# Sheet1.net
KiCad netlist of a schematic drawn in Altium Designer
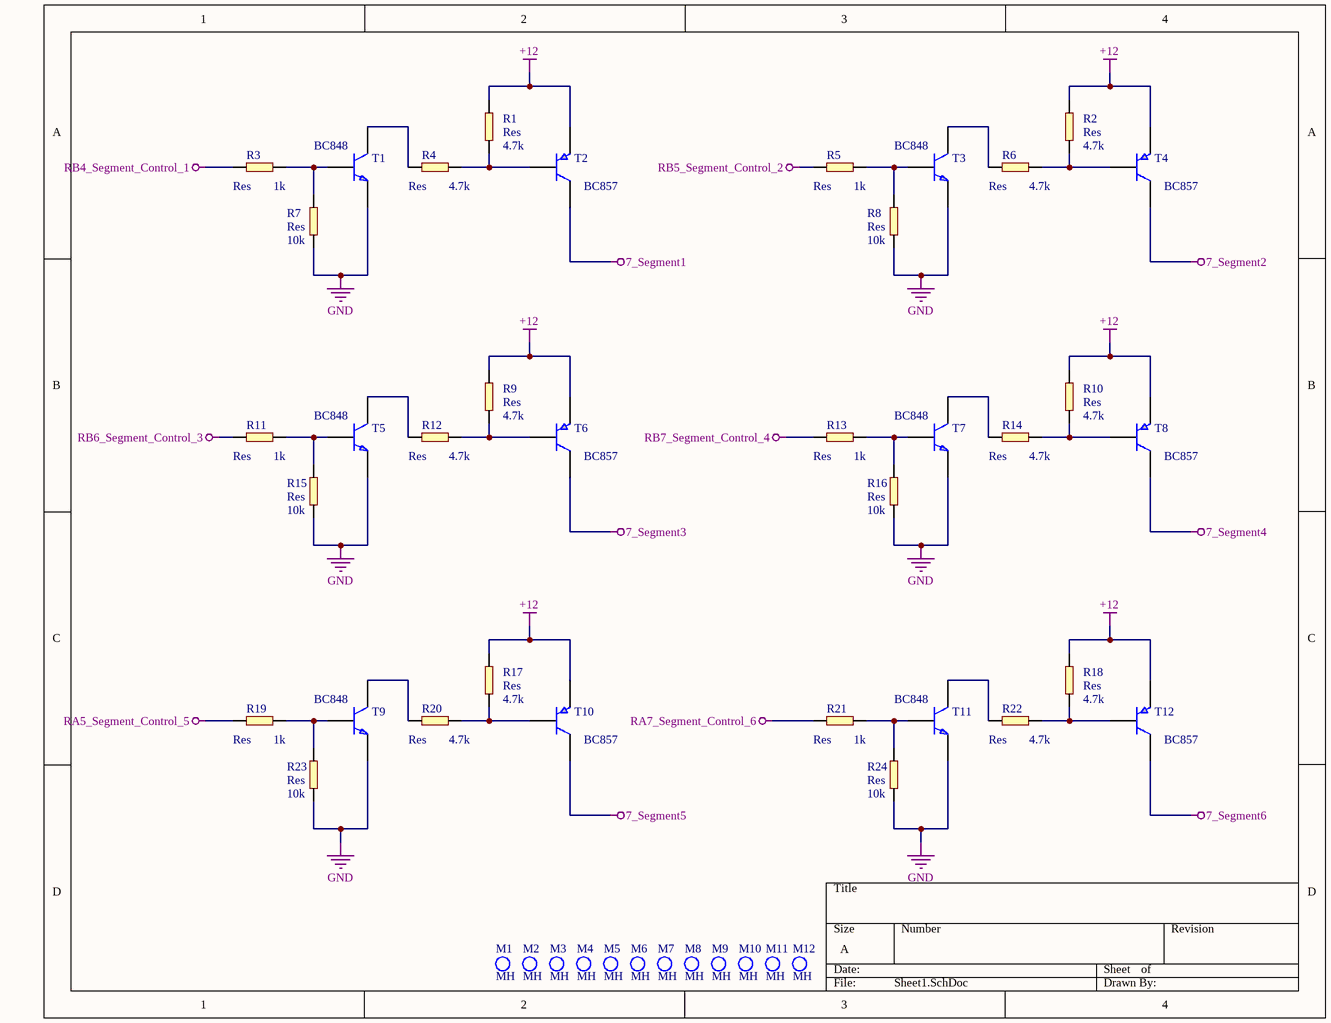
[diagram p0: Sheet1.SchDoc]

(export (version "E")
  (design (tool "Eeschema 10.0.6"))
  (components
    (comp (ref "M1")
      (value "MH")
      (footprint "Mounting hole")
      (libsource (lib "Dinesh_New_Integrated_Library") (part "MH"))
    )
    (comp (ref "M2")
      (value "MH")
      (footprint "Mounting hole")
      (libsource (lib "Dinesh_New_Integrated_Library") (part "MH"))
    )
    (comp (ref "M3")
      (value "MH")
      (footprint "Mounting hole")
      (libsource (lib "Dinesh_New_Integrated_Library") (part "MH"))
    )
    (comp (ref "M4")
      (value "MH")
      (footprint "Mounting hole")
      (libsource (lib "Dinesh_New_Integrated_Library") (part "MH"))
    )
    (comp (ref "M5")
      (value "MH")
      (footprint "Mounting hole")
      (libsource (lib "Dinesh_New_Integrated_Library") (part "MH"))
    )
    (comp (ref "M6")
      (value "MH")
      (footprint "Mounting hole")
      (libsource (lib "Dinesh_New_Integrated_Library") (part "MH"))
    )
    (comp (ref "M7")
      (value "MH")
      (footprint "Mounting hole")
      (libsource (lib "Dinesh_New_Integrated_Library") (part "MH"))
    )
    (comp (ref "M8")
      (value "MH")
      (footprint "Mounting hole")
      (libsource (lib "Dinesh_New_Integrated_Library") (part "MH"))
    )
    (comp (ref "M9")
      (value "MH")
      (footprint "Mounting hole")
      (libsource (lib "Dinesh_New_Integrated_Library") (part "MH"))
    )
    (comp (ref "M10")
      (value "MH")
      (footprint "Mounting hole")
      (libsource (lib "Dinesh_New_Integrated_Library") (part "MH"))
    )
    (comp (ref "M11")
      (value "MH")
      (footprint "Mounting hole")
      (libsource (lib "Dinesh_New_Integrated_Library") (part "MH"))
    )
    (comp (ref "M12")
      (value "MH")
      (footprint "Mounting hole")
      (libsource (lib "Dinesh_New_Integrated_Library") (part "MH"))
    )
    (comp (ref "R1")
      (value "Res")
      (footprint "RES0805")
      (description "Res0805")
      (fields (field (name "ALTIUM_VALUE") "4.7k"))
      (libsource (lib "") (part "Resistor_2"))
    )
    (comp (ref "R2")
      (value "Res")
      (footprint "RES0805")
      (description "Res0805")
      (fields (field (name "ALTIUM_VALUE") "4.7k"))
      (libsource (lib "") (part "Resistor_2"))
    )
    (comp (ref "R3")
      (value "Res")
      (footprint "RES0805")
      (description "Res0805")
      (fields (field (name "ALTIUM_VALUE") "1k"))
      (libsource (lib "") (part "Resistor_1"))
    )
    (comp (ref "R4")
      (value "Res")
      (footprint "RES0805")
      (description "Res0805")
      (fields (field (name "ALTIUM_VALUE") "4.7k"))
      (libsource (lib "") (part "Resistor_1"))
    )
    (comp (ref "R5")
      (value "Res")
      (footprint "RES0805")
      (description "Res0805")
      (fields (field (name "ALTIUM_VALUE") "1k"))
      (libsource (lib "") (part "Resistor_1"))
    )
    (comp (ref "R6")
      (value "Res")
      (footprint "RES0805")
      (description "Res0805")
      (fields (field (name "ALTIUM_VALUE") "4.7k"))
      (libsource (lib "") (part "Resistor_1"))
    )
    (comp (ref "R7")
      (value "Res")
      (footprint "RES0805")
      (description "Res0805")
      (fields (field (name "ALTIUM_VALUE") "10k"))
      (libsource (lib "Dinesh_New_Integrated_Library") (part "Resistor"))
    )
    (comp (ref "R8")
      (value "Res")
      (footprint "RES0805")
      (description "Res0805")
      (fields (field (name "ALTIUM_VALUE") "10k"))
      (libsource (lib "Dinesh_New_Integrated_Library") (part "Resistor"))
    )
    (comp (ref "R9")
      (value "Res")
      (footprint "RES0805")
      (description "Res0805")
      (fields (field (name "ALTIUM_VALUE") "4.7k"))
      (libsource (lib "") (part "Resistor_2"))
    )
    (comp (ref "R10")
      (value "Res")
      (footprint "RES0805")
      (description "Res0805")
      (fields (field (name "ALTIUM_VALUE") "4.7k"))
      (libsource (lib "") (part "Resistor_2"))
    )
    (comp (ref "R11")
      (value "Res")
      (footprint "RES0805")
      (description "Res0805")
      (fields (field (name "ALTIUM_VALUE") "1k"))
      (libsource (lib "") (part "Resistor_1"))
    )
    (comp (ref "R12")
      (value "Res")
      (footprint "RES0805")
      (description "Res0805")
      (fields (field (name "ALTIUM_VALUE") "4.7k"))
      (libsource (lib "") (part "Resistor_1"))
    )
    (comp (ref "R13")
      (value "Res")
      (footprint "RES0805")
      (description "Res0805")
      (fields (field (name "ALTIUM_VALUE") "1k"))
      (libsource (lib "") (part "Resistor_1"))
    )
    (comp (ref "R14")
      (value "Res")
      (footprint "RES0805")
      (description "Res0805")
      (fields (field (name "ALTIUM_VALUE") "4.7k"))
      (libsource (lib "") (part "Resistor_1"))
    )
    (comp (ref "R15")
      (value "Res")
      (footprint "RES0805")
      (description "Res0805")
      (fields (field (name "ALTIUM_VALUE") "10k"))
      (libsource (lib "Dinesh_New_Integrated_Library") (part "Resistor"))
    )
    (comp (ref "R16")
      (value "Res")
      (footprint "RES0805")
      (description "Res0805")
      (fields (field (name "ALTIUM_VALUE") "10k"))
      (libsource (lib "Dinesh_New_Integrated_Library") (part "Resistor"))
    )
    (comp (ref "R17")
      (value "Res")
      (footprint "RES0805")
      (description "Res0805")
      (fields (field (name "ALTIUM_VALUE") "4.7k"))
      (libsource (lib "") (part "Resistor_2"))
    )
    (comp (ref "R18")
      (value "Res")
      (footprint "RES0805")
      (description "Res0805")
      (fields (field (name "ALTIUM_VALUE") "4.7k"))
      (libsource (lib "") (part "Resistor_2"))
    )
    (comp (ref "R19")
      (value "Res")
      (footprint "RES0805")
      (description "Res0805")
      (fields (field (name "ALTIUM_VALUE") "1k"))
      (libsource (lib "") (part "Resistor_1"))
    )
    (comp (ref "R20")
      (value "Res")
      (footprint "RES0805")
      (description "Res0805")
      (fields (field (name "ALTIUM_VALUE") "4.7k"))
      (libsource (lib "") (part "Resistor_1"))
    )
    (comp (ref "R21")
      (value "Res")
      (footprint "RES0805")
      (description "Res0805")
      (fields (field (name "ALTIUM_VALUE") "1k"))
      (libsource (lib "") (part "Resistor_1"))
    )
    (comp (ref "R22")
      (value "Res")
      (footprint "RES0805")
      (description "Res0805")
      (fields (field (name "ALTIUM_VALUE") "4.7k"))
      (libsource (lib "") (part "Resistor_1"))
    )
    (comp (ref "R23")
      (value "Res")
      (footprint "RES0805")
      (description "Res0805")
      (fields (field (name "ALTIUM_VALUE") "10k"))
      (libsource (lib "Dinesh_New_Integrated_Library") (part "Resistor"))
    )
    (comp (ref "R24")
      (value "Res")
      (footprint "RES0805")
      (description "Res0805")
      (fields (field (name "ALTIUM_VALUE") "10k"))
      (libsource (lib "Dinesh_New_Integrated_Library") (part "Resistor"))
    )
    (comp (ref "T1")
      (value "BC848")
      (footprint "SOT23")
      (description "TRANSISTOR")
      (libsource (lib "Dinesh_New_Integrated_Library") (part "BC848"))
    )
    (comp (ref "T2")
      (value "BC857")
      (footprint "SOT23")
      (libsource (lib "Dinesh_New_Integrated_Library") (part "BC857"))
    )
    (comp (ref "T3")
      (value "BC848")
      (footprint "SOT23")
      (description "TRANSISTOR")
      (libsource (lib "Dinesh_New_Integrated_Library") (part "BC848"))
    )
    (comp (ref "T4")
      (value "BC857")
      (footprint "SOT23")
      (libsource (lib "Dinesh_New_Integrated_Library") (part "BC857"))
    )
    (comp (ref "T5")
      (value "BC848")
      (footprint "SOT23")
      (description "TRANSISTOR")
      (libsource (lib "Dinesh_New_Integrated_Library") (part "BC848"))
    )
    (comp (ref "T6")
      (value "BC857")
      (footprint "SOT23")
      (libsource (lib "Dinesh_New_Integrated_Library") (part "BC857"))
    )
    (comp (ref "T7")
      (value "BC848")
      (footprint "SOT23")
      (description "TRANSISTOR")
      (libsource (lib "Dinesh_New_Integrated_Library") (part "BC848"))
    )
    (comp (ref "T8")
      (value "BC857")
      (footprint "SOT23")
      (libsource (lib "Dinesh_New_Integrated_Library") (part "BC857"))
    )
    (comp (ref "T9")
      (value "BC848")
      (footprint "SOT23")
      (description "TRANSISTOR")
      (libsource (lib "Dinesh_New_Integrated_Library") (part "BC848"))
    )
    (comp (ref "T10")
      (value "BC857")
      (footprint "SOT23")
      (libsource (lib "Dinesh_New_Integrated_Library") (part "BC857"))
    )
    (comp (ref "T11")
      (value "BC848")
      (footprint "SOT23")
      (description "TRANSISTOR")
      (libsource (lib "Dinesh_New_Integrated_Library") (part "BC848"))
    )
    (comp (ref "T12")
      (value "BC857")
      (footprint "SOT23")
      (libsource (lib "Dinesh_New_Integrated_Library") (part "BC857"))
    )
  )
  (nets
    (net (code "1") (name "+12") (class "Default")
      (node (ref "R1") (pin "2") (pinfunction "b_2") (pintype "passive"))
      (node (ref "R10") (pin "2") (pinfunction "b_2") (pintype "passive"))
      (node (ref "R17") (pin "2") (pinfunction "b_2") (pintype "passive"))
      (node (ref "R18") (pin "2") (pinfunction "b_2") (pintype "passive"))
      (node (ref "R2") (pin "2") (pinfunction "b_2") (pintype "passive"))
      (node (ref "R9") (pin "2") (pinfunction "b_2") (pintype "passive"))
      (node (ref "T10") (pin "2") (pinfunction "E_2") (pintype "passive"))
      (node (ref "T12") (pin "2") (pinfunction "E_2") (pintype "passive"))
      (node (ref "T2") (pin "2") (pinfunction "E_2") (pintype "passive"))
      (node (ref "T4") (pin "2") (pinfunction "E_2") (pintype "passive"))
      (node (ref "T6") (pin "2") (pinfunction "E_2") (pintype "passive"))
      (node (ref "T8") (pin "2") (pinfunction "E_2") (pintype "passive"))
    )
    (net (code "2") (name "7_Segment1") (class "Default")
      (node (ref "T2") (pin "3") (pinfunction "C_3") (pintype "passive"))
    )
    (net (code "3") (name "7_Segment2") (class "Default")
      (node (ref "T4") (pin "3") (pinfunction "C_3") (pintype "passive"))
    )
    (net (code "4") (name "7_Segment3") (class "Default")
      (node (ref "T6") (pin "3") (pinfunction "C_3") (pintype "passive"))
    )
    (net (code "5") (name "7_Segment4") (class "Default")
      (node (ref "T8") (pin "3") (pinfunction "C_3") (pintype "passive"))
    )
    (net (code "6") (name "7_Segment5") (class "Default")
      (node (ref "T10") (pin "3") (pinfunction "C_3") (pintype "passive"))
    )
    (net (code "7") (name "7_Segment6") (class "Default")
      (node (ref "T12") (pin "3") (pinfunction "C_3") (pintype "passive"))
    )
    (net (code "8") (name "GND") (class "Default")
      (node (ref "R15") (pin "2") (pinfunction "b_2") (pintype "passive"))
      (node (ref "R16") (pin "2") (pinfunction "b_2") (pintype "passive"))
      (node (ref "R23") (pin "2") (pinfunction "b_2") (pintype "passive"))
      (node (ref "R24") (pin "2") (pinfunction "b_2") (pintype "passive"))
      (node (ref "R7") (pin "2") (pinfunction "b_2") (pintype "passive"))
      (node (ref "R8") (pin "2") (pinfunction "b_2") (pintype "passive"))
      (node (ref "T1") (pin "2") (pinfunction "E_2") (pintype "passive"))
      (node (ref "T11") (pin "2") (pinfunction "E_2") (pintype "passive"))
      (node (ref "T3") (pin "2") (pinfunction "E_2") (pintype "passive"))
      (node (ref "T5") (pin "2") (pinfunction "E_2") (pintype "passive"))
      (node (ref "T7") (pin "2") (pinfunction "E_2") (pintype "passive"))
      (node (ref "T9") (pin "2") (pinfunction "E_2") (pintype "passive"))
    )
    (net (code "9") (name "Net-(R1-a)") (class "Default")
      (node (ref "R1") (pin "1") (pinfunction "a_1") (pintype "passive"))
      (node (ref "R4") (pin "1") (pinfunction "a_1") (pintype "passive"))
      (node (ref "T2") (pin "1") (pinfunction "B_1") (pintype "passive"))
    )
    (net (code "10") (name "Net-(R2-a)") (class "Default")
      (node (ref "R2") (pin "1") (pinfunction "a_1") (pintype "passive"))
      (node (ref "R6") (pin "1") (pinfunction "a_1") (pintype "passive"))
      (node (ref "T4") (pin "1") (pinfunction "B_1") (pintype "passive"))
    )
    (net (code "11") (name "Net-(R3-a)") (class "Default")
      (node (ref "R3") (pin "1") (pinfunction "a_1") (pintype "passive"))
      (node (ref "R7") (pin "1") (pinfunction "a_1") (pintype "passive"))
      (node (ref "T1") (pin "1") (pinfunction "B_1") (pintype "passive"))
    )
    (net (code "12") (name "Net-(R4-b)") (class "Default")
      (node (ref "R4") (pin "2") (pinfunction "b_2") (pintype "passive"))
      (node (ref "T1") (pin "3") (pinfunction "C_3") (pintype "passive"))
    )
    (net (code "13") (name "Net-(R5-a)") (class "Default")
      (node (ref "R5") (pin "1") (pinfunction "a_1") (pintype "passive"))
      (node (ref "R8") (pin "1") (pinfunction "a_1") (pintype "passive"))
      (node (ref "T3") (pin "1") (pinfunction "B_1") (pintype "passive"))
    )
    (net (code "14") (name "Net-(R6-b)") (class "Default")
      (node (ref "R6") (pin "2") (pinfunction "b_2") (pintype "passive"))
      (node (ref "T3") (pin "3") (pinfunction "C_3") (pintype "passive"))
    )
    (net (code "15") (name "Net-(R10-a)") (class "Default")
      (node (ref "R10") (pin "1") (pinfunction "a_1") (pintype "passive"))
      (node (ref "R14") (pin "1") (pinfunction "a_1") (pintype "passive"))
      (node (ref "T8") (pin "1") (pinfunction "B_1") (pintype "passive"))
    )
    (net (code "16") (name "Net-(R11-a)") (class "Default")
      (node (ref "R11") (pin "1") (pinfunction "a_1") (pintype "passive"))
      (node (ref "R15") (pin "1") (pinfunction "a_1") (pintype "passive"))
      (node (ref "T5") (pin "1") (pinfunction "B_1") (pintype "passive"))
    )
    (net (code "17") (name "Net-(R12-a)") (class "Default")
      (node (ref "R12") (pin "1") (pinfunction "a_1") (pintype "passive"))
      (node (ref "R9") (pin "1") (pinfunction "a_1") (pintype "passive"))
      (node (ref "T6") (pin "1") (pinfunction "B_1") (pintype "passive"))
    )
    (net (code "18") (name "Net-(R12-b)") (class "Default")
      (node (ref "R12") (pin "2") (pinfunction "b_2") (pintype "passive"))
      (node (ref "T5") (pin "3") (pinfunction "C_3") (pintype "passive"))
    )
    (net (code "19") (name "Net-(R13-a)") (class "Default")
      (node (ref "R13") (pin "1") (pinfunction "a_1") (pintype "passive"))
      (node (ref "R16") (pin "1") (pinfunction "a_1") (pintype "passive"))
      (node (ref "T7") (pin "1") (pinfunction "B_1") (pintype "passive"))
    )
    (net (code "20") (name "Net-(R14-b)") (class "Default")
      (node (ref "R14") (pin "2") (pinfunction "b_2") (pintype "passive"))
      (node (ref "T7") (pin "3") (pinfunction "C_3") (pintype "passive"))
    )
    (net (code "21") (name "Net-(R17-a)") (class "Default")
      (node (ref "R17") (pin "1") (pinfunction "a_1") (pintype "passive"))
      (node (ref "R20") (pin "1") (pinfunction "a_1") (pintype "passive"))
      (node (ref "T10") (pin "1") (pinfunction "B_1") (pintype "passive"))
    )
    (net (code "22") (name "Net-(R18-a)") (class "Default")
      (node (ref "R18") (pin "1") (pinfunction "a_1") (pintype "passive"))
      (node (ref "R22") (pin "1") (pinfunction "a_1") (pintype "passive"))
      (node (ref "T12") (pin "1") (pinfunction "B_1") (pintype "passive"))
    )
    (net (code "23") (name "Net-(R19-a)") (class "Default")
      (node (ref "R19") (pin "1") (pinfunction "a_1") (pintype "passive"))
      (node (ref "R23") (pin "1") (pinfunction "a_1") (pintype "passive"))
      (node (ref "T9") (pin "1") (pinfunction "B_1") (pintype "passive"))
    )
    (net (code "24") (name "Net-(R20-b)") (class "Default")
      (node (ref "R20") (pin "2") (pinfunction "b_2") (pintype "passive"))
      (node (ref "T9") (pin "3") (pinfunction "C_3") (pintype "passive"))
    )
    (net (code "25") (name "Net-(R21-a)") (class "Default")
      (node (ref "R21") (pin "1") (pinfunction "a_1") (pintype "passive"))
      (node (ref "R24") (pin "1") (pinfunction "a_1") (pintype "passive"))
      (node (ref "T11") (pin "1") (pinfunction "B_1") (pintype "passive"))
    )
    (net (code "26") (name "Net-(R22-b)") (class "Default")
      (node (ref "R22") (pin "2") (pinfunction "b_2") (pintype "passive"))
      (node (ref "T11") (pin "3") (pinfunction "C_3") (pintype "passive"))
    )
    (net (code "27") (name "RA5_Segment_Control_5") (class "Default")
      (node (ref "R19") (pin "2") (pinfunction "b_2") (pintype "passive"))
    )
    (net (code "28") (name "RA7_Segment_Control_6") (class "Default")
      (node (ref "R21") (pin "2") (pinfunction "b_2") (pintype "passive"))
    )
    (net (code "29") (name "RB4_Segment_Control_1") (class "Default")
      (node (ref "R3") (pin "2") (pinfunction "b_2") (pintype "passive"))
    )
    (net (code "30") (name "RB5_Segment_Control_2") (class "Default")
      (node (ref "R5") (pin "2") (pinfunction "b_2") (pintype "passive"))
    )
    (net (code "31") (name "RB6_Segment_Control_3") (class "Default")
      (node (ref "R11") (pin "2") (pinfunction "b_2") (pintype "passive"))
    )
    (net (code "32") (name "RB7_Segment_Control_4") (class "Default")
      (node (ref "R13") (pin "2") (pinfunction "b_2") (pintype "passive"))
    )
  )
)
